# seismo.net
KiCad netlist of a schematic drawn in EAGLE
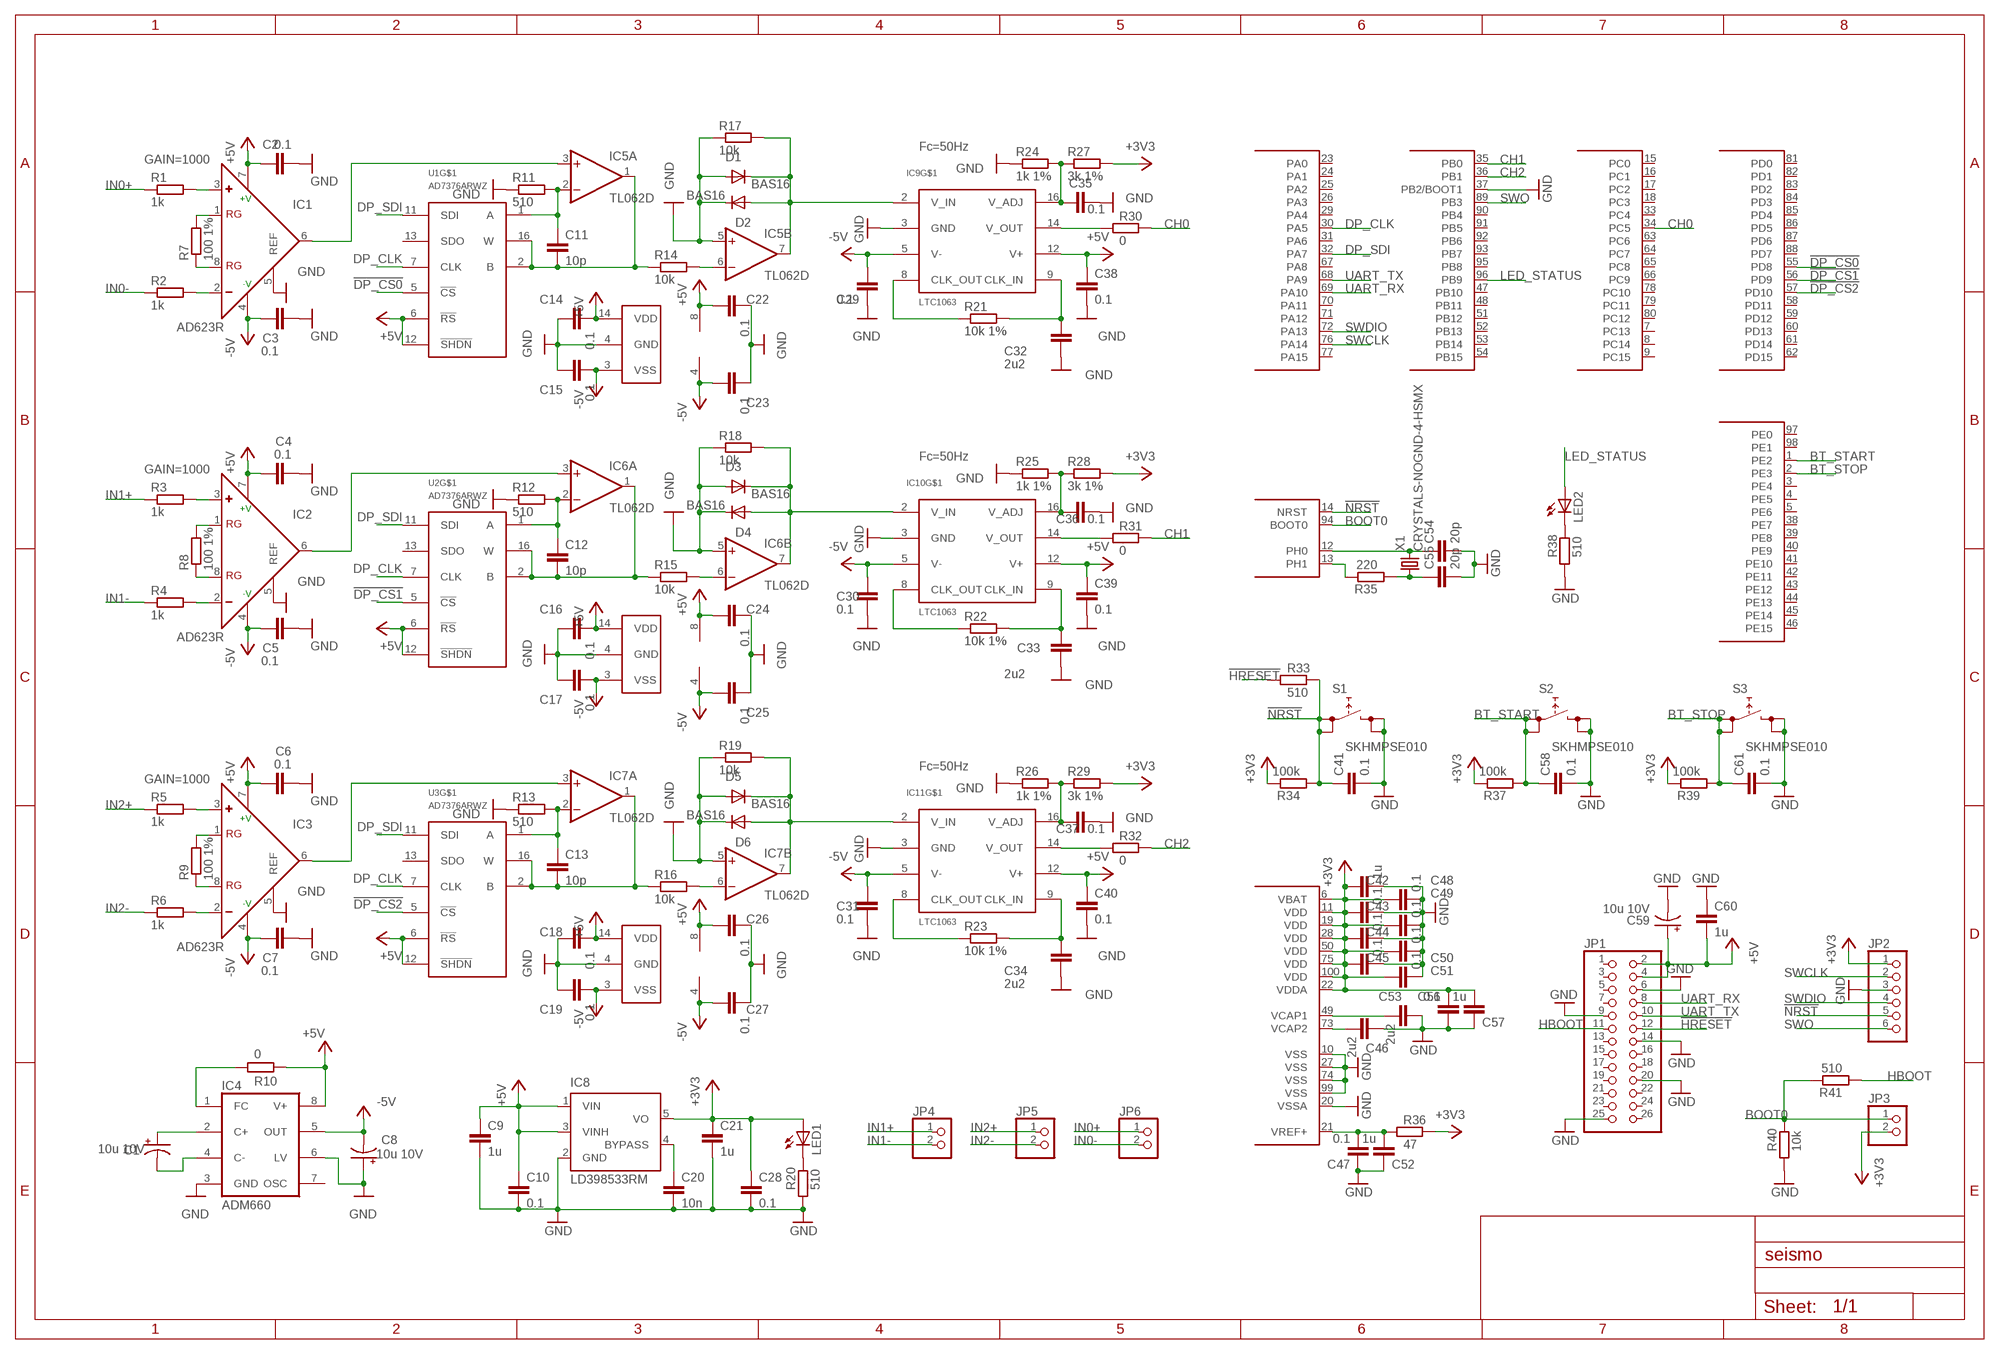
[diagram p0: schematic, sheet 1]

(export (version "E")
  (design (tool "Eeschema 10.0.6"))
  (components
    (comp (ref "C1")
      (value "10u 10V")
      (footprint "eagle-import:SMC_A")
      (libsource (lib "eagle-import") (part "CPOL-USSMCA"))
    )
    (comp (ref "C2")
      (value "0.1")
      (footprint "eagle-import:C0805")
      (libsource (lib "eagle-import") (part "C-EUC0805"))
    )
    (comp (ref "C3")
      (value "0.1")
      (footprint "eagle-import:C0805")
      (libsource (lib "eagle-import") (part "C-EUC0805"))
    )
    (comp (ref "C4")
      (value "0.1")
      (footprint "eagle-import:C0805")
      (libsource (lib "eagle-import") (part "C-EUC0805"))
    )
    (comp (ref "C5")
      (value "0.1")
      (footprint "eagle-import:C0805")
      (libsource (lib "eagle-import") (part "C-EUC0805"))
    )
    (comp (ref "C6")
      (value "0.1")
      (footprint "eagle-import:C0805")
      (libsource (lib "eagle-import") (part "C-EUC0805"))
    )
    (comp (ref "C7")
      (value "0.1")
      (footprint "eagle-import:C0805")
      (libsource (lib "eagle-import") (part "C-EUC0805"))
    )
    (comp (ref "C8")
      (value "10u 10V")
      (footprint "eagle-import:SMC_A")
      (libsource (lib "eagle-import") (part "CPOL-USSMCA"))
    )
    (comp (ref "C9")
      (value "1u")
      (footprint "eagle-import:C0805")
      (libsource (lib "eagle-import") (part "C-EUC0805"))
    )
    (comp (ref "C10")
      (value "0.1")
      (footprint "eagle-import:C0805")
      (libsource (lib "eagle-import") (part "C-EUC0805"))
    )
    (comp (ref "C11")
      (value "10p")
      (footprint "eagle-import:C0805")
      (libsource (lib "eagle-import") (part "C-EUC0805"))
    )
    (comp (ref "C12")
      (value "10p")
      (footprint "eagle-import:C0805")
      (libsource (lib "eagle-import") (part "C-EUC0805"))
    )
    (comp (ref "C13")
      (value "10p")
      (footprint "eagle-import:C0805")
      (libsource (lib "eagle-import") (part "C-EUC0805"))
    )
    (comp (ref "C14")
      (value "0.1")
      (footprint "eagle-import:C0805")
      (libsource (lib "eagle-import") (part "C-EUC0805"))
    )
    (comp (ref "C15")
      (value "0.1")
      (footprint "eagle-import:C0805")
      (libsource (lib "eagle-import") (part "C-EUC0805"))
    )
    (comp (ref "C16")
      (value "0.1")
      (footprint "eagle-import:C0805")
      (libsource (lib "eagle-import") (part "C-EUC0805"))
    )
    (comp (ref "C17")
      (value "0.1")
      (footprint "eagle-import:C0805")
      (libsource (lib "eagle-import") (part "C-EUC0805"))
    )
    (comp (ref "C18")
      (value "0.1")
      (footprint "eagle-import:C0805")
      (libsource (lib "eagle-import") (part "C-EUC0805"))
    )
    (comp (ref "C19")
      (value "0.1")
      (footprint "eagle-import:C0805")
      (libsource (lib "eagle-import") (part "C-EUC0805"))
    )
    (comp (ref "C20")
      (value "10n")
      (footprint "eagle-import:C0805")
      (libsource (lib "eagle-import") (part "C-EUC0805"))
    )
    (comp (ref "C21")
      (value "1u")
      (footprint "eagle-import:C0805")
      (libsource (lib "eagle-import") (part "C-EUC0805"))
    )
    (comp (ref "C22")
      (value "0.1")
      (footprint "eagle-import:C0805")
      (libsource (lib "eagle-import") (part "C-EUC0805"))
    )
    (comp (ref "C23")
      (value "0.1")
      (footprint "eagle-import:C0805")
      (libsource (lib "eagle-import") (part "C-EUC0805"))
    )
    (comp (ref "C24")
      (value "0.1")
      (footprint "eagle-import:C0805")
      (libsource (lib "eagle-import") (part "C-EUC0805"))
    )
    (comp (ref "C25")
      (value "0.1")
      (footprint "eagle-import:C0805")
      (libsource (lib "eagle-import") (part "C-EUC0805"))
    )
    (comp (ref "C26")
      (value "0.1")
      (footprint "eagle-import:C0805")
      (libsource (lib "eagle-import") (part "C-EUC0805"))
    )
    (comp (ref "C27")
      (value "0.1")
      (footprint "eagle-import:C0805")
      (libsource (lib "eagle-import") (part "C-EUC0805"))
    )
    (comp (ref "C28")
      (value "0.1")
      (footprint "eagle-import:C0805")
      (libsource (lib "eagle-import") (part "C-EUC0805"))
    )
    (comp (ref "C29")
      (value "0.1")
      (footprint "eagle-import:C0805")
      (libsource (lib "eagle-import") (part "C-EUC0805"))
    )
    (comp (ref "C30")
      (value "0.1")
      (footprint "eagle-import:C0805")
      (libsource (lib "eagle-import") (part "C-EUC0805"))
    )
    (comp (ref "C31")
      (value "0.1")
      (footprint "eagle-import:C0805")
      (libsource (lib "eagle-import") (part "C-EUC0805"))
    )
    (comp (ref "C32")
      (value "2u2")
      (footprint "eagle-import:C0805")
      (libsource (lib "eagle-import") (part "C-EUC0805"))
    )
    (comp (ref "C33")
      (value "2u2")
      (footprint "eagle-import:C0805")
      (libsource (lib "eagle-import") (part "C-EUC0805"))
    )
    (comp (ref "C34")
      (value "2u2")
      (footprint "eagle-import:C0805")
      (libsource (lib "eagle-import") (part "C-EUC0805"))
    )
    (comp (ref "C35")
      (value "0.1")
      (footprint "eagle-import:C0805")
      (libsource (lib "eagle-import") (part "C-EUC0805"))
    )
    (comp (ref "C36")
      (value "0.1")
      (footprint "eagle-import:C0805")
      (libsource (lib "eagle-import") (part "C-EUC0805"))
    )
    (comp (ref "C37")
      (value "0.1")
      (footprint "eagle-import:C0805")
      (libsource (lib "eagle-import") (part "C-EUC0805"))
    )
    (comp (ref "C38")
      (value "0.1")
      (footprint "eagle-import:C0805")
      (libsource (lib "eagle-import") (part "C-EUC0805"))
    )
    (comp (ref "C39")
      (value "0.1")
      (footprint "eagle-import:C0805")
      (libsource (lib "eagle-import") (part "C-EUC0805"))
    )
    (comp (ref "C40")
      (value "0.1")
      (footprint "eagle-import:C0805")
      (libsource (lib "eagle-import") (part "C-EUC0805"))
    )
    (comp (ref "C41")
      (value "0.1")
      (footprint "eagle-import:C0805")
      (libsource (lib "eagle-import") (part "C-EUC0805"))
    )
    (comp (ref "C42")
      (value "1u")
      (footprint "eagle-import:C0805")
      (libsource (lib "eagle-import") (part "C-EUC0805"))
    )
    (comp (ref "C43")
      (value "0.1")
      (footprint "eagle-import:C0805")
      (libsource (lib "eagle-import") (part "C-EUC0805"))
    )
    (comp (ref "C44")
      (value "0.1")
      (footprint "eagle-import:C0805")
      (libsource (lib "eagle-import") (part "C-EUC0805"))
    )
    (comp (ref "C45")
      (value "0.1")
      (footprint "eagle-import:C0805")
      (libsource (lib "eagle-import") (part "C-EUC0805"))
    )
    (comp (ref "C46")
      (value "2u2")
      (footprint "eagle-import:C0805")
      (libsource (lib "eagle-import") (part "C-EUC0805"))
    )
    (comp (ref "C47")
      (value "0.1")
      (footprint "eagle-import:C0805")
      (libsource (lib "eagle-import") (part "C-EUC0805"))
    )
    (comp (ref "C48")
      (value "0.1")
      (footprint "eagle-import:C0805")
      (libsource (lib "eagle-import") (part "C-EUC0805"))
    )
    (comp (ref "C49")
      (value "0.1")
      (footprint "eagle-import:C0805")
      (libsource (lib "eagle-import") (part "C-EUC0805"))
    )
    (comp (ref "C50")
      (value "0.1")
      (footprint "eagle-import:C0805")
      (libsource (lib "eagle-import") (part "C-EUC0805"))
    )
    (comp (ref "C51")
      (value "0.1")
      (footprint "eagle-import:C0805")
      (libsource (lib "eagle-import") (part "C-EUC0805"))
    )
    (comp (ref "C52")
      (value "1u")
      (footprint "eagle-import:C0805")
      (libsource (lib "eagle-import") (part "C-EUC0805"))
    )
    (comp (ref "C53")
      (value "2u2")
      (footprint "eagle-import:C0805")
      (libsource (lib "eagle-import") (part "C-EUC0805"))
    )
    (comp (ref "C54")
      (value "20p")
      (footprint "eagle-import:C0805")
      (libsource (lib "eagle-import") (part "C-EUC0805"))
    )
    (comp (ref "C55")
      (value "20p")
      (footprint "eagle-import:C0805")
      (libsource (lib "eagle-import") (part "C-EUC0805"))
    )
    (comp (ref "C56")
      (value "0.1")
      (footprint "eagle-import:C0805")
      (libsource (lib "eagle-import") (part "C-EUC0805"))
    )
    (comp (ref "C57")
      (value "1u")
      (footprint "eagle-import:C0805")
      (libsource (lib "eagle-import") (part "C-EUC0805"))
    )
    (comp (ref "C58")
      (value "0.1")
      (footprint "eagle-import:C0805")
      (libsource (lib "eagle-import") (part "C-EUC0805"))
    )
    (comp (ref "C59")
      (value "10u 10V")
      (footprint "eagle-import:SMC_A")
      (libsource (lib "eagle-import") (part "CPOL-USSMCA"))
    )
    (comp (ref "C60")
      (value "1u")
      (footprint "eagle-import:C0805")
      (libsource (lib "eagle-import") (part "C-EUC0805"))
    )
    (comp (ref "C61")
      (value "0.1")
      (footprint "eagle-import:C0805")
      (libsource (lib "eagle-import") (part "C-EUC0805"))
    )
    (comp (ref "D1")
      (value "BAS16")
      (footprint "eagle-import:SOT23")
      (libsource (lib "eagle-import") (part "BAS16"))
    )
    (comp (ref "D2")
      (value "BAS16")
      (footprint "eagle-import:SOT23")
      (libsource (lib "eagle-import") (part "BAS16"))
    )
    (comp (ref "D3")
      (value "BAS16")
      (footprint "eagle-import:SOT23")
      (libsource (lib "eagle-import") (part "BAS16"))
    )
    (comp (ref "D4")
      (value "BAS16")
      (footprint "eagle-import:SOT23")
      (libsource (lib "eagle-import") (part "BAS16"))
    )
    (comp (ref "D5")
      (value "BAS16")
      (footprint "eagle-import:SOT23")
      (libsource (lib "eagle-import") (part "BAS16"))
    )
    (comp (ref "D6")
      (value "BAS16")
      (footprint "eagle-import:SOT23")
      (libsource (lib "eagle-import") (part "BAS16"))
    )
    (comp (ref "IC1")
      (value "AD623R")
      (footprint "eagle-import:SO8")
      (fields (field (name "MPN") "AD623ARZ."))
      (libsource (lib "eagle-import") (part "AD623R"))
    )
    (comp (ref "IC2")
      (value "AD623R")
      (footprint "eagle-import:SO8")
      (fields (field (name "MPN") "AD623ARZ."))
      (libsource (lib "eagle-import") (part "AD623R"))
    )
    (comp (ref "IC3")
      (value "AD623R")
      (footprint "eagle-import:SO8")
      (fields (field (name "MPN") "AD623ARZ."))
      (libsource (lib "eagle-import") (part "AD623R"))
    )
    (comp (ref "IC4")
      (value "ADM660")
      (footprint "eagle-import:SO8")
      (libsource (lib "eagle-import") (part "ADM660"))
    )
    (comp (ref "IC5")
      (value "TL062D")
      (footprint "eagle-import:SO08")
      (libsource (lib "eagle-import") (part "TL062D"))
    )
    (comp (ref "IC6")
      (value "TL062D")
      (footprint "eagle-import:SO08")
      (libsource (lib "eagle-import") (part "TL062D"))
    )
    (comp (ref "IC7")
      (value "TL062D")
      (footprint "eagle-import:SO08")
      (libsource (lib "eagle-import") (part "TL062D"))
    )
    (comp (ref "IC8")
      (value "LD398533RM")
      (footprint "eagle-import:SOT23-5L")
      (libsource (lib "eagle-import") (part "LD3985M33R"))
    )
    (comp (ref "IC9")
      (value "LTC1063")
      (footprint "eagle-import:SOIC127P1032X264-16N")
      (libsource (lib "eagle-import") (part "LTC1063"))
    )
    (comp (ref "IC10")
      (value "LTC1063")
      (footprint "eagle-import:SOIC127P1032X264-16N")
      (libsource (lib "eagle-import") (part "LTC1063"))
    )
    (comp (ref "IC11")
      (value "LTC1063")
      (footprint "eagle-import:SOIC127P1032X264-16N")
      (libsource (lib "eagle-import") (part "LTC1063"))
    )
    (comp (ref "JP1")
      (value "PINHD-2X13")
      (footprint "eagle-import:2X13")
      (libsource (lib "eagle-import") (part "PINHD-2X13"))
    )
    (comp (ref "JP2")
      (value "PINHD-1X6")
      (footprint "eagle-import:1X06")
      (libsource (lib "eagle-import") (part "PINHD-1X6"))
    )
    (comp (ref "JP3")
      (value "PINHD-1X2")
      (footprint "eagle-import:1X02")
      (libsource (lib "eagle-import") (part "PINHD-1X2"))
    )
    (comp (ref "JP4")
      (value "PINHD-1X2")
      (footprint "eagle-import:1X02")
      (libsource (lib "eagle-import") (part "PINHD-1X2"))
    )
    (comp (ref "JP5")
      (value "PINHD-1X2")
      (footprint "eagle-import:1X02")
      (libsource (lib "eagle-import") (part "PINHD-1X2"))
    )
    (comp (ref "JP6")
      (value "PINHD-1X2")
      (footprint "eagle-import:1X02")
      (libsource (lib "eagle-import") (part "PINHD-1X2"))
    )
    (comp (ref "LED1")
      (value "LEDCHIPLED_1206")
      (footprint "eagle-import:CHIPLED_1206")
      (libsource (lib "eagle-import") (part "LEDCHIPLED_1206"))
    )
    (comp (ref "LED2")
      (value "LEDCHIPLED_1206")
      (footprint "eagle-import:CHIPLED_1206")
      (libsource (lib "eagle-import") (part "LEDCHIPLED_1206"))
    )
    (comp (ref "R1")
      (value "1k")
      (footprint "eagle-import:R0805W")
      (libsource (lib "eagle-import") (part "R-EU_R0805W"))
    )
    (comp (ref "R2")
      (value "1k")
      (footprint "eagle-import:R0805W")
      (libsource (lib "eagle-import") (part "R-EU_R0805W"))
    )
    (comp (ref "R3")
      (value "1k")
      (footprint "eagle-import:R0805W")
      (libsource (lib "eagle-import") (part "R-EU_R0805W"))
    )
    (comp (ref "R4")
      (value "1k")
      (footprint "eagle-import:R0805W")
      (libsource (lib "eagle-import") (part "R-EU_R0805W"))
    )
    (comp (ref "R5")
      (value "1k")
      (footprint "eagle-import:R0805W")
      (libsource (lib "eagle-import") (part "R-EU_R0805W"))
    )
    (comp (ref "R6")
      (value "1k")
      (footprint "eagle-import:R0805W")
      (libsource (lib "eagle-import") (part "R-EU_R0805W"))
    )
    (comp (ref "R7")
      (value "100 1%")
      (footprint "eagle-import:R0805W")
      (libsource (lib "eagle-import") (part "R-EU_R0805W"))
    )
    (comp (ref "R8")
      (value "100 1%")
      (footprint "eagle-import:R0805W")
      (libsource (lib "eagle-import") (part "R-EU_R0805W"))
    )
    (comp (ref "R9")
      (value "100 1%")
      (footprint "eagle-import:R0805W")
      (libsource (lib "eagle-import") (part "R-EU_R0805W"))
    )
    (comp (ref "R10")
      (value "0")
      (footprint "eagle-import:R0805W")
      (libsource (lib "eagle-import") (part "R-EU_R0805W"))
    )
    (comp (ref "R11")
      (value "510")
      (footprint "eagle-import:R0805W")
      (libsource (lib "eagle-import") (part "R-EU_R0805W"))
    )
    (comp (ref "R12")
      (value "510")
      (footprint "eagle-import:R0805W")
      (libsource (lib "eagle-import") (part "R-EU_R0805W"))
    )
    (comp (ref "R13")
      (value "510")
      (footprint "eagle-import:R0805W")
      (libsource (lib "eagle-import") (part "R-EU_R0805W"))
    )
    (comp (ref "R14")
      (value "10k")
      (footprint "eagle-import:R0805W")
      (libsource (lib "eagle-import") (part "R-EU_R0805W"))
    )
    (comp (ref "R15")
      (value "10k")
      (footprint "eagle-import:R0805W")
      (libsource (lib "eagle-import") (part "R-EU_R0805W"))
    )
    (comp (ref "R16")
      (value "10k")
      (footprint "eagle-import:R0805W")
      (libsource (lib "eagle-import") (part "R-EU_R0805W"))
    )
    (comp (ref "R17")
      (value "10k")
      (footprint "eagle-import:R0805W")
      (libsource (lib "eagle-import") (part "R-EU_R0805W"))
    )
    (comp (ref "R18")
      (value "10k")
      (footprint "eagle-import:R0805W")
      (libsource (lib "eagle-import") (part "R-EU_R0805W"))
    )
    (comp (ref "R19")
      (value "10k")
      (footprint "eagle-import:R0805W")
      (libsource (lib "eagle-import") (part "R-EU_R0805W"))
    )
    (comp (ref "R20")
      (value "510")
      (footprint "eagle-import:R0805W")
      (libsource (lib "eagle-import") (part "R-EU_R0805W"))
    )
    (comp (ref "R21")
      (value "10k 1%")
      (footprint "eagle-import:R0805W")
      (libsource (lib "eagle-import") (part "R-EU_R0805W"))
    )
    (comp (ref "R22")
      (value "10k 1%")
      (footprint "eagle-import:R0805W")
      (libsource (lib "eagle-import") (part "R-EU_R0805W"))
    )
    (comp (ref "R23")
      (value "10k 1%")
      (footprint "eagle-import:R0805W")
      (libsource (lib "eagle-import") (part "R-EU_R0805W"))
    )
    (comp (ref "R24")
      (value "1k 1%")
      (footprint "eagle-import:R0805W")
      (libsource (lib "eagle-import") (part "R-EU_R0805W"))
    )
    (comp (ref "R25")
      (value "1k 1%")
      (footprint "eagle-import:R0805W")
      (libsource (lib "eagle-import") (part "R-EU_R0805W"))
    )
    (comp (ref "R26")
      (value "1k 1%")
      (footprint "eagle-import:R0805W")
      (libsource (lib "eagle-import") (part "R-EU_R0805W"))
    )
    (comp (ref "R27")
      (value "3k 1%")
      (footprint "eagle-import:R0805W")
      (libsource (lib "eagle-import") (part "R-EU_R0805W"))
    )
    (comp (ref "R28")
      (value "3k 1%")
      (footprint "eagle-import:R0805W")
      (libsource (lib "eagle-import") (part "R-EU_R0805W"))
    )
    (comp (ref "R29")
      (value "3k 1%")
      (footprint "eagle-import:R0805W")
      (libsource (lib "eagle-import") (part "R-EU_R0805W"))
    )
    (comp (ref "R30")
      (value "0")
      (footprint "eagle-import:R0805W")
      (libsource (lib "eagle-import") (part "R-EU_R0805W"))
    )
    (comp (ref "R31")
      (value "0")
      (footprint "eagle-import:R0805W")
      (libsource (lib "eagle-import") (part "R-EU_R0805W"))
    )
    (comp (ref "R32")
      (value "0")
      (footprint "eagle-import:R0805W")
      (libsource (lib "eagle-import") (part "R-EU_R0805W"))
    )
    (comp (ref "R33")
      (value "510")
      (footprint "eagle-import:R0805W")
      (libsource (lib "eagle-import") (part "R-EU_R0805W"))
    )
    (comp (ref "R34")
      (value "100k")
      (footprint "eagle-import:R0805W")
      (libsource (lib "eagle-import") (part "R-EU_R0805W"))
    )
    (comp (ref "R35")
      (value "220")
      (footprint "eagle-import:R0805W")
      (libsource (lib "eagle-import") (part "R-EU_R0805W"))
    )
    (comp (ref "R36")
      (value "47")
      (footprint "eagle-import:R0805W")
      (libsource (lib "eagle-import") (part "R-EU_R0805W"))
    )
    (comp (ref "R37")
      (value "100k")
      (footprint "eagle-import:R0805W")
      (libsource (lib "eagle-import") (part "R-EU_R0805W"))
    )
    (comp (ref "R38")
      (value "510")
      (footprint "eagle-import:R0805W")
      (libsource (lib "eagle-import") (part "R-EU_R0805W"))
    )
    (comp (ref "R39")
      (value "100k")
      (footprint "eagle-import:R0805W")
      (libsource (lib "eagle-import") (part "R-EU_R0805W"))
    )
    (comp (ref "R40")
      (value "10k")
      (footprint "eagle-import:R0805W")
      (libsource (lib "eagle-import") (part "R-EU_R0805W"))
    )
    (comp (ref "R41")
      (value "510")
      (footprint "eagle-import:R0805W")
      (libsource (lib "eagle-import") (part "R-EU_R0805W"))
    )
    (comp (ref "S1")
      (value "SKHMPSE010")
      (footprint "eagle-import:SKHMPXE010")
      (libsource (lib "eagle-import") (part "SKHMPE010S"))
    )
    (comp (ref "S2")
      (value "SKHMPSE010")
      (footprint "eagle-import:SKHMPXE010")
      (libsource (lib "eagle-import") (part "SKHMPE010S"))
    )
    (comp (ref "S3")
      (value "SKHMPSE010")
      (footprint "eagle-import:SKHMPXE010")
      (libsource (lib "eagle-import") (part "SKHMPE010S"))
    )
    (comp (ref "U1")
      (value "AD7376ARWZ")
      (footprint "eagle-import:SO-16W")
      (libsource (lib "eagle-import") (part "AD7376ARWZ"))
    )
    (comp (ref "U2")
      (value "AD7376ARWZ")
      (footprint "eagle-import:SO-16W")
      (libsource (lib "eagle-import") (part "AD7376ARWZ"))
    )
    (comp (ref "U3")
      (value "AD7376ARWZ")
      (footprint "eagle-import:SO-16W")
      (libsource (lib "eagle-import") (part "AD7376ARWZ"))
    )
    (comp (ref "U4")
      (value "STM32F4-100")
      (footprint "eagle-import:SQFP-S-14X14-100")
      (libsource (lib "eagle-import") (part "STM32F4-100"))
    )
    (comp (ref "X1")
      (value "CRYSTALS-NOGND-4-HSMX")
      (footprint "eagle-import:HC49-4-HSMX")
      (libsource (lib "eagle-import") (part "CRYSTALS-NOGND-4-HSMX"))
    )
  )
  (nets
    (net (code "1") (name "+3V3") (class "Default")
      (node (ref "C21") (pin "1") (pinfunction "1_1") (pintype "passive"))
      (node (ref "C28") (pin "1") (pinfunction "1_1") (pintype "passive"))
      (node (ref "C42") (pin "1") (pinfunction "1_1") (pintype "passive"))
      (node (ref "C43") (pin "1") (pinfunction "1_1") (pintype "passive"))
      (node (ref "C44") (pin "1") (pinfunction "1_1") (pintype "passive"))
      (node (ref "C45") (pin "1") (pinfunction "1_1") (pintype "passive"))
      (node (ref "C48") (pin "1") (pinfunction "1_1") (pintype "passive"))
      (node (ref "C49") (pin "1") (pinfunction "1_1") (pintype "passive"))
      (node (ref "C50") (pin "1") (pinfunction "1_1") (pintype "passive"))
      (node (ref "C51") (pin "1") (pinfunction "1_1") (pintype "passive"))
      (node (ref "C56") (pin "2") (pinfunction "2_2") (pintype "passive"))
      (node (ref "C57") (pin "2") (pinfunction "2_2") (pintype "passive"))
      (node (ref "IC8") (pin "5") (pinfunction "VO_5") (pintype "output"))
      (node (ref "JP2") (pin "1") (pinfunction "1_1") (pintype "passive"))
      (node (ref "JP3") (pin "2") (pinfunction "2_2") (pintype "passive"))
      (node (ref "LED1") (pin "A") (pinfunction "A_A") (pintype "passive"))
      (node (ref "R27") (pin "2") (pinfunction "2_2") (pintype "passive"))
      (node (ref "R28") (pin "2") (pinfunction "2_2") (pintype "passive"))
      (node (ref "R29") (pin "2") (pinfunction "2_2") (pintype "passive"))
      (node (ref "R34") (pin "2") (pinfunction "2_2") (pintype "passive"))
      (node (ref "R36") (pin "2") (pinfunction "2_2") (pintype "passive"))
      (node (ref "R37") (pin "2") (pinfunction "2_2") (pintype "passive"))
      (node (ref "R39") (pin "2") (pinfunction "2_2") (pintype "passive"))
      (node (ref "U4") (pin "100") (pinfunction "VDD_100") (pintype "power_in"))
      (node (ref "U4") (pin "11") (pinfunction "VDD_11") (pintype "power_in"))
      (node (ref "U4") (pin "19") (pinfunction "VDD_19") (pintype "power_in"))
      (node (ref "U4") (pin "22") (pinfunction "VDDA_22") (pintype "power_in"))
      (node (ref "U4") (pin "28") (pinfunction "VDD_28") (pintype "power_in"))
      (node (ref "U4") (pin "50") (pinfunction "VDD_50") (pintype "power_in"))
      (node (ref "U4") (pin "6") (pinfunction "VBAT_6") (pintype "power_in"))
      (node (ref "U4") (pin "75") (pinfunction "VDD_75") (pintype "power_in"))
    )
    (net (code "2") (name "+5V") (class "Default")
      (node (ref "C10") (pin "1") (pinfunction "1_1") (pintype "passive"))
      (node (ref "C14") (pin "2") (pinfunction "2_2") (pintype "passive"))
      (node (ref "C16") (pin "2") (pinfunction "2_2") (pintype "passive"))
      (node (ref "C18") (pin "2") (pinfunction "2_2") (pintype "passive"))
      (node (ref "C2") (pin "1") (pinfunction "1_1") (pintype "passive"))
      (node (ref "C22") (pin "1") (pinfunction "1_1") (pintype "passive"))
      (node (ref "C24") (pin "1") (pinfunction "1_1") (pintype "passive"))
      (node (ref "C26") (pin "1") (pinfunction "1_1") (pintype "passive"))
      (node (ref "C38") (pin "1") (pinfunction "1_1") (pintype "passive"))
      (node (ref "C39") (pin "1") (pinfunction "1_1") (pintype "passive"))
      (node (ref "C4") (pin "1") (pinfunction "1_1") (pintype "passive"))
      (node (ref "C40") (pin "1") (pinfunction "1_1") (pintype "passive"))
      (node (ref "C59") (pin "+") (pinfunction "+_+") (pintype "passive"))
      (node (ref "C6") (pin "1") (pinfunction "1_1") (pintype "passive"))
      (node (ref "C60") (pin "2") (pinfunction "2_2") (pintype "passive"))
      (node (ref "C9") (pin "1") (pinfunction "1_1") (pintype "passive"))
      (node (ref "IC1") (pin "7") (pinfunction "+V_7") (pintype "power_in"))
      (node (ref "IC10") (pin "12") (pinfunction "V+_12") (pintype "power_in"))
      (node (ref "IC11") (pin "12") (pinfunction "V+_12") (pintype "power_in"))
      (node (ref "IC2") (pin "7") (pinfunction "+V_7") (pintype "power_in"))
      (node (ref "IC3") (pin "7") (pinfunction "+V_7") (pintype "power_in"))
      (node (ref "IC4") (pin "8") (pinfunction "V+_8") (pintype "power_in"))
      (node (ref "IC5") (pin "8") (pinfunction "V+_8") (pintype "power_in"))
      (node (ref "IC6") (pin "8") (pinfunction "V+_8") (pintype "power_in"))
      (node (ref "IC7") (pin "8") (pinfunction "V+_8") (pintype "power_in"))
      (node (ref "IC8") (pin "1") (pinfunction "VIN_1") (pintype "input"))
      (node (ref "IC8") (pin "3") (pinfunction "VINH_3") (pintype "input"))
      (node (ref "IC9") (pin "12") (pinfunction "V+_12") (pintype "power_in"))
      (node (ref "JP1") (pin "2") (pinfunction "2_2") (pintype "passive"))
      (node (ref "JP1") (pin "4") (pinfunction "4_4") (pintype "passive"))
      (node (ref "R10") (pin "2") (pinfunction "2_2") (pintype "passive"))
      (node (ref "U1") (pin "12") (pinfunction "~{SHDN}_12") (pintype "input"))
      (node (ref "U1") (pin "14") (pinfunction "VDD_14") (pintype "power_in"))
      (node (ref "U1") (pin "6") (pinfunction "~{RS}_6") (pintype "input"))
      (node (ref "U2") (pin "12") (pinfunction "~{SHDN}_12") (pintype "input"))
      (node (ref "U2") (pin "14") (pinfunction "VDD_14") (pintype "power_in"))
      (node (ref "U2") (pin "6") (pinfunction "~{RS}_6") (pintype "input"))
      (node (ref "U3") (pin "12") (pinfunction "~{SHDN}_12") (pintype "input"))
      (node (ref "U3") (pin "14") (pinfunction "VDD_14") (pintype "power_in"))
      (node (ref "U3") (pin "6") (pinfunction "~{RS}_6") (pintype "input"))
    )
    (net (code "3") (name "-5V") (class "Default")
      (node (ref "C15") (pin "2") (pinfunction "2_2") (pintype "passive"))
      (node (ref "C17") (pin "2") (pinfunction "2_2") (pintype "passive"))
      (node (ref "C19") (pin "2") (pinfunction "2_2") (pintype "passive"))
      (node (ref "C23") (pin "1") (pinfunction "1_1") (pintype "passive"))
      (node (ref "C25") (pin "1") (pinfunction "1_1") (pintype "passive"))
      (node (ref "C27") (pin "1") (pinfunction "1_1") (pintype "passive"))
      (node (ref "C29") (pin "1") (pinfunction "1_1") (pintype "passive"))
      (node (ref "C3") (pin "1") (pinfunction "1_1") (pintype "passive"))
      (node (ref "C30") (pin "1") (pinfunction "1_1") (pintype "passive"))
      (node (ref "C31") (pin "1") (pinfunction "1_1") (pintype "passive"))
      (node (ref "C5") (pin "1") (pinfunction "1_1") (pintype "passive"))
      (node (ref "C7") (pin "1") (pinfunction "1_1") (pintype "passive"))
      (node (ref "C8") (pin "-") (pinfunction "-_-") (pintype "passive"))
      (node (ref "IC1") (pin "4") (pinfunction "-V_4") (pintype "power_in"))
      (node (ref "IC10") (pin "5") (pinfunction "V-_5") (pintype "power_in"))
      (node (ref "IC11") (pin "5") (pinfunction "V-_5") (pintype "power_in"))
      (node (ref "IC2") (pin "4") (pinfunction "-V_4") (pintype "power_in"))
      (node (ref "IC3") (pin "4") (pinfunction "-V_4") (pintype "power_in"))
      (node (ref "IC4") (pin "5") (pinfunction "OUT_5") (pintype "power_in"))
      (node (ref "IC5") (pin "4") (pinfunction "V-_4") (pintype "power_in"))
      (node (ref "IC6") (pin "4") (pinfunction "V-_4") (pintype "power_in"))
      (node (ref "IC7") (pin "4") (pinfunction "V-_4") (pintype "power_in"))
      (node (ref "IC9") (pin "5") (pinfunction "V-_5") (pintype "power_in"))
      (node (ref "U1") (pin "3") (pinfunction "VSS_3") (pintype "power_in"))
      (node (ref "U2") (pin "3") (pinfunction "VSS_3") (pintype "power_in"))
      (node (ref "U3") (pin "3") (pinfunction "VSS_3") (pintype "power_in"))
    )
    (net (code "4") (name "/BOOT0") (class "Default")
      (node (ref "JP3") (pin "1") (pinfunction "1_1") (pintype "passive"))
      (node (ref "R40") (pin "2") (pinfunction "2_2") (pintype "passive"))
      (node (ref "R41") (pin "2") (pinfunction "2_2") (pintype "passive"))
      (node (ref "U4") (pin "94") (pinfunction "BOOT0_94") (pintype "bidirectional"))
    )
    (net (code "5") (name "/BT_START") (class "Default")
      (node (ref "C58") (pin "1") (pinfunction "1_1") (pintype "passive"))
      (node (ref "R37") (pin "1") (pinfunction "1_1") (pintype "passive"))
      (node (ref "S2") (pin "1") (pinfunction "1.1_1") (pintype "passive"))
      (node (ref "S2") (pin "2") (pinfunction "1.2_2") (pintype "passive"))
      (node (ref "U4") (pin "1") (pinfunction "PE2_1") (pintype "bidirectional"))
    )
    (net (code "6") (name "/BT_STOP") (class "Default")
      (node (ref "C61") (pin "1") (pinfunction "1_1") (pintype "passive"))
      (node (ref "R39") (pin "1") (pinfunction "1_1") (pintype "passive"))
      (node (ref "S3") (pin "1") (pinfunction "1.1_1") (pintype "passive"))
      (node (ref "S3") (pin "2") (pinfunction "1.2_2") (pintype "passive"))
      (node (ref "U4") (pin "2") (pinfunction "PE3_2") (pintype "bidirectional"))
    )
    (net (code "7") (name "/CH0") (class "Default")
      (node (ref "R30") (pin "2") (pinfunction "2_2") (pintype "passive"))
      (node (ref "U4") (pin "34") (pinfunction "PC5_34") (pintype "bidirectional"))
    )
    (net (code "8") (name "/CH1") (class "Default")
      (node (ref "R31") (pin "2") (pinfunction "2_2") (pintype "passive"))
      (node (ref "U4") (pin "35") (pinfunction "PB0_35") (pintype "bidirectional"))
    )
    (net (code "9") (name "/CH2") (class "Default")
      (node (ref "R32") (pin "2") (pinfunction "2_2") (pintype "passive"))
      (node (ref "U4") (pin "36") (pinfunction "PB1_36") (pintype "bidirectional"))
    )
    (net (code "10") (name "/DP_CLK") (class "Default")
      (node (ref "U1") (pin "7") (pinfunction "CLK_7") (pintype "input"))
      (node (ref "U2") (pin "7") (pinfunction "CLK_7") (pintype "input"))
      (node (ref "U3") (pin "7") (pinfunction "CLK_7") (pintype "input"))
      (node (ref "U4") (pin "30") (pinfunction "PA5_30") (pintype "bidirectional"))
    )
    (net (code "11") (name "/DP_SDI") (class "Default")
      (node (ref "U1") (pin "11") (pinfunction "SDI_11") (pintype "input"))
      (node (ref "U2") (pin "11") (pinfunction "SDI_11") (pintype "input"))
      (node (ref "U3") (pin "11") (pinfunction "SDI_11") (pintype "input"))
      (node (ref "U4") (pin "32") (pinfunction "PA7_32") (pintype "bidirectional"))
    )
    (net (code "12") (name "/HBOOT") (class "Default")
      (node (ref "JP1") (pin "11") (pinfunction "11_11") (pintype "passive"))
      (node (ref "R41") (pin "1") (pinfunction "1_1") (pintype "passive"))
    )
    (net (code "13") (name "/IN0+") (class "Default")
      (node (ref "JP6") (pin "1") (pinfunction "1_1") (pintype "passive"))
      (node (ref "R1") (pin "1") (pinfunction "1_1") (pintype "passive"))
    )
    (net (code "14") (name "/IN0-") (class "Default")
      (node (ref "JP6") (pin "2") (pinfunction "2_2") (pintype "passive"))
      (node (ref "R2") (pin "1") (pinfunction "1_1") (pintype "passive"))
    )
    (net (code "15") (name "/IN1+") (class "Default")
      (node (ref "JP4") (pin "1") (pinfunction "1_1") (pintype "passive"))
      (node (ref "R3") (pin "1") (pinfunction "1_1") (pintype "passive"))
    )
    (net (code "16") (name "/IN1-") (class "Default")
      (node (ref "JP4") (pin "2") (pinfunction "2_2") (pintype "passive"))
      (node (ref "R4") (pin "1") (pinfunction "1_1") (pintype "passive"))
    )
    (net (code "17") (name "/IN2+") (class "Default")
      (node (ref "JP5") (pin "1") (pinfunction "1_1") (pintype "passive"))
      (node (ref "R5") (pin "1") (pinfunction "1_1") (pintype "passive"))
    )
    (net (code "18") (name "/IN2-") (class "Default")
      (node (ref "JP5") (pin "2") (pinfunction "2_2") (pintype "passive"))
      (node (ref "R6") (pin "1") (pinfunction "1_1") (pintype "passive"))
    )
    (net (code "19") (name "/LED_STATUS") (class "Default")
      (node (ref "LED2") (pin "A") (pinfunction "A_A") (pintype "passive"))
      (node (ref "U4") (pin "96") (pinfunction "PB9_96") (pintype "bidirectional"))
    )
    (net (code "20") (name "/SWCLK") (class "Default")
      (node (ref "JP2") (pin "2") (pinfunction "2_2") (pintype "passive"))
      (node (ref "U4") (pin "76") (pinfunction "PA14_76") (pintype "bidirectional"))
    )
    (net (code "21") (name "/SWDIO") (class "Default")
      (node (ref "JP2") (pin "4") (pinfunction "4_4") (pintype "passive"))
      (node (ref "U4") (pin "72") (pinfunction "PA13_72") (pintype "bidirectional"))
    )
    (net (code "22") (name "/SWO") (class "Default")
      (node (ref "JP2") (pin "6") (pinfunction "6_6") (pintype "passive"))
      (node (ref "U4") (pin "89") (pinfunction "PB3_89") (pintype "bidirectional"))
    )
    (net (code "23") (name "/UART_RX") (class "Default")
      (node (ref "JP1") (pin "8") (pinfunction "8_8") (pintype "passive"))
      (node (ref "U4") (pin "69") (pinfunction "PA10_69") (pintype "bidirectional"))
    )
    (net (code "24") (name "/UART_TX") (class "Default")
      (node (ref "JP1") (pin "10") (pinfunction "10_10") (pintype "passive"))
      (node (ref "U4") (pin "68") (pinfunction "PA9_68") (pintype "bidirectional"))
    )
    (net (code "25") (name "/~{DP_CS0}") (class "Default")
      (node (ref "U1") (pin "5") (pinfunction "~{CS}_5") (pintype "input"))
      (node (ref "U4") (pin "55") (pinfunction "PD8_55") (pintype "bidirectional"))
    )
    (net (code "26") (name "/~{DP_CS1}") (class "Default")
      (node (ref "U2") (pin "5") (pinfunction "~{CS}_5") (pintype "input"))
      (node (ref "U4") (pin "56") (pinfunction "PD9_56") (pintype "bidirectional"))
    )
    (net (code "27") (name "/~{DP_CS2}") (class "Default")
      (node (ref "U3") (pin "5") (pinfunction "~{CS}_5") (pintype "input"))
      (node (ref "U4") (pin "57") (pinfunction "PD10_57") (pintype "bidirectional"))
    )
    (net (code "28") (name "/~{HRESET}") (class "Default")
      (node (ref "JP1") (pin "12") (pinfunction "12_12") (pintype "passive"))
      (node (ref "R33") (pin "1") (pinfunction "1_1") (pintype "passive"))
    )
    (net (code "29") (name "/~{NRST}") (class "Default")
      (node (ref "C41") (pin "1") (pinfunction "1_1") (pintype "passive"))
      (node (ref "JP2") (pin "5") (pinfunction "5_5") (pintype "passive"))
      (node (ref "R33") (pin "2") (pinfunction "2_2") (pintype "passive"))
      (node (ref "R34") (pin "1") (pinfunction "1_1") (pintype "passive"))
      (node (ref "S1") (pin "1") (pinfunction "1.1_1") (pintype "passive"))
      (node (ref "S1") (pin "2") (pinfunction "1.2_2") (pintype "passive"))
      (node (ref "U4") (pin "14") (pinfunction "NRST_14") (pintype "bidirectional"))
    )
    (net (code "30") (name "GND") (class "Default")
      (node (ref "C10") (pin "2") (pinfunction "2_2") (pintype "passive"))
      (node (ref "C14") (pin "1") (pinfunction "1_1") (pintype "passive"))
      (node (ref "C15") (pin "1") (pinfunction "1_1") (pintype "passive"))
      (node (ref "C16") (pin "1") (pinfunction "1_1") (pintype "passive"))
      (node (ref "C17") (pin "1") (pinfunction "1_1") (pintype "passive"))
      (node (ref "C18") (pin "1") (pinfunction "1_1") (pintype "passive"))
      (node (ref "C19") (pin "1") (pinfunction "1_1") (pintype "passive"))
      (node (ref "C2") (pin "2") (pinfunction "2_2") (pintype "passive"))
      (node (ref "C20") (pin "2") (pinfunction "2_2") (pintype "passive"))
      (node (ref "C21") (pin "2") (pinfunction "2_2") (pintype "passive"))
      (node (ref "C22") (pin "2") (pinfunction "2_2") (pintype "passive"))
      (node (ref "C23") (pin "2") (pinfunction "2_2") (pintype "passive"))
      (node (ref "C24") (pin "2") (pinfunction "2_2") (pintype "passive"))
      (node (ref "C25") (pin "2") (pinfunction "2_2") (pintype "passive"))
      (node (ref "C26") (pin "2") (pinfunction "2_2") (pintype "passive"))
      (node (ref "C27") (pin "2") (pinfunction "2_2") (pintype "passive"))
      (node (ref "C28") (pin "2") (pinfunction "2_2") (pintype "passive"))
      (node (ref "C29") (pin "2") (pinfunction "2_2") (pintype "passive"))
      (node (ref "C3") (pin "2") (pinfunction "2_2") (pintype "passive"))
      (node (ref "C30") (pin "2") (pinfunction "2_2") (pintype "passive"))
      (node (ref "C31") (pin "2") (pinfunction "2_2") (pintype "passive"))
      (node (ref "C32") (pin "2") (pinfunction "2_2") (pintype "passive"))
      (node (ref "C33") (pin "2") (pinfunction "2_2") (pintype "passive"))
      (node (ref "C34") (pin "2") (pinfunction "2_2") (pintype "passive"))
      (node (ref "C35") (pin "2") (pinfunction "2_2") (pintype "passive"))
      (node (ref "C36") (pin "2") (pinfunction "2_2") (pintype "passive"))
      (node (ref "C37") (pin "2") (pinfunction "2_2") (pintype "passive"))
      (node (ref "C38") (pin "2") (pinfunction "2_2") (pintype "passive"))
      (node (ref "C39") (pin "2") (pinfunction "2_2") (pintype "passive"))
      (node (ref "C4") (pin "2") (pinfunction "2_2") (pintype "passive"))
      (node (ref "C40") (pin "2") (pinfunction "2_2") (pintype "passive"))
      (node (ref "C41") (pin "2") (pinfunction "2_2") (pintype "passive"))
      (node (ref "C42") (pin "2") (pinfunction "2_2") (pintype "passive"))
      (node (ref "C43") (pin "2") (pinfunction "2_2") (pintype "passive"))
      (node (ref "C44") (pin "2") (pinfunction "2_2") (pintype "passive"))
      (node (ref "C45") (pin "2") (pinfunction "2_2") (pintype "passive"))
      (node (ref "C46") (pin "1") (pinfunction "1_1") (pintype "passive"))
      (node (ref "C47") (pin "1") (pinfunction "1_1") (pintype "passive"))
      (node (ref "C48") (pin "2") (pinfunction "2_2") (pintype "passive"))
      (node (ref "C49") (pin "2") (pinfunction "2_2") (pintype "passive"))
      (node (ref "C5") (pin "2") (pinfunction "2_2") (pintype "passive"))
      (node (ref "C50") (pin "2") (pinfunction "2_2") (pintype "passive"))
      (node (ref "C51") (pin "2") (pinfunction "2_2") (pintype "passive"))
      (node (ref "C52") (pin "1") (pinfunction "1_1") (pintype "passive"))
      (node (ref "C53") (pin "1") (pinfunction "1_1") (pintype "passive"))
      (node (ref "C54") (pin "2") (pinfunction "2_2") (pintype "passive"))
      (node (ref "C55") (pin "2") (pinfunction "2_2") (pintype "passive"))
      (node (ref "C56") (pin "1") (pinfunction "1_1") (pintype "passive"))
      (node (ref "C57") (pin "1") (pinfunction "1_1") (pintype "passive"))
      (node (ref "C58") (pin "2") (pinfunction "2_2") (pintype "passive"))
      (node (ref "C59") (pin "-") (pinfunction "-_-") (pintype "passive"))
      (node (ref "C6") (pin "2") (pinfunction "2_2") (pintype "passive"))
      (node (ref "C60") (pin "1") (pinfunction "1_1") (pintype "passive"))
      (node (ref "C61") (pin "2") (pinfunction "2_2") (pintype "passive"))
      (node (ref "C7") (pin "2") (pinfunction "2_2") (pintype "passive"))
      (node (ref "C8") (pin "+") (pinfunction "+_+") (pintype "passive"))
      (node (ref "C9") (pin "2") (pinfunction "2_2") (pintype "passive"))
      (node (ref "D1") (pin "1") (pinfunction "A_1") (pintype "passive"))
      (node (ref "D2") (pin "3") (pinfunction "C_3") (pintype "passive"))
      (node (ref "D3") (pin "1") (pinfunction "A_1") (pintype "passive"))
      (node (ref "D4") (pin "3") (pinfunction "C_3") (pintype "passive"))
      (node (ref "D5") (pin "1") (pinfunction "A_1") (pintype "passive"))
      (node (ref "D6") (pin "3") (pinfunction "C_3") (pintype "passive"))
      (node (ref "IC1") (pin "5") (pinfunction "REF_5") (pintype "passive"))
      (node (ref "IC10") (pin "3") (pinfunction "GND_3") (pintype "power_in"))
      (node (ref "IC11") (pin "3") (pinfunction "GND_3") (pintype "power_in"))
      (node (ref "IC2") (pin "5") (pinfunction "REF_5") (pintype "passive"))
      (node (ref "IC3") (pin "5") (pinfunction "REF_5") (pintype "passive"))
      (node (ref "IC4") (pin "3") (pinfunction "GND_3") (pintype "power_in"))
      (node (ref "IC4") (pin "6") (pinfunction "LV_6") (pintype "passive"))
      (node (ref "IC5") (pin "5") (pinfunction "+IN_5") (pintype "input"))
      (node (ref "IC6") (pin "5") (pinfunction "+IN_5") (pintype "input"))
      (node (ref "IC7") (pin "5") (pinfunction "+IN_5") (pintype "input"))
      (node (ref "IC8") (pin "2") (pinfunction "GND_2") (pintype "power_in"))
      (node (ref "IC9") (pin "3") (pinfunction "GND_3") (pintype "power_in"))
      (node (ref "JP1") (pin "14") (pinfunction "14_14") (pintype "passive"))
      (node (ref "JP1") (pin "20") (pinfunction "20_20") (pintype "passive"))
      (node (ref "JP1") (pin "25") (pinfunction "25_25") (pintype "passive"))
      (node (ref "JP1") (pin "6") (pinfunction "6_6") (pintype "passive"))
      (node (ref "JP1") (pin "9") (pinfunction "9_9") (pintype "passive"))
      (node (ref "JP2") (pin "3") (pinfunction "3_3") (pintype "passive"))
      (node (ref "R11") (pin "1") (pinfunction "1_1") (pintype "passive"))
      (node (ref "R12") (pin "1") (pinfunction "1_1") (pintype "passive"))
      (node (ref "R13") (pin "1") (pinfunction "1_1") (pintype "passive"))
      (node (ref "R17") (pin "1") (pinfunction "1_1") (pintype "passive"))
      (node (ref "R18") (pin "1") (pinfunction "1_1") (pintype "passive"))
      (node (ref "R19") (pin "1") (pinfunction "1_1") (pintype "passive"))
      (node (ref "R20") (pin "1") (pinfunction "1_1") (pintype "passive"))
      (node (ref "R24") (pin "1") (pinfunction "1_1") (pintype "passive"))
      (node (ref "R25") (pin "1") (pinfunction "1_1") (pintype "passive"))
      (node (ref "R26") (pin "1") (pinfunction "1_1") (pintype "passive"))
      (node (ref "R38") (pin "1") (pinfunction "1_1") (pintype "passive"))
      (node (ref "R40") (pin "1") (pinfunction "1_1") (pintype "passive"))
      (node (ref "S1") (pin "3") (pinfunction "2.1_3") (pintype "passive"))
      (node (ref "S1") (pin "4") (pinfunction "2.2_4") (pintype "passive"))
      (node (ref "S2") (pin "3") (pinfunction "2.1_3") (pintype "passive"))
      (node (ref "S2") (pin "4") (pinfunction "2.2_4") (pintype "passive"))
      (node (ref "S3") (pin "3") (pinfunction "2.1_3") (pintype "passive"))
      (node (ref "S3") (pin "4") (pinfunction "2.2_4") (pintype "passive"))
      (node (ref "U1") (pin "4") (pinfunction "GND_4") (pintype "power_in"))
      (node (ref "U2") (pin "4") (pinfunction "GND_4") (pintype "power_in"))
      (node (ref "U3") (pin "4") (pinfunction "GND_4") (pintype "power_in"))
      (node (ref "U4") (pin "10") (pinfunction "VSS_10") (pintype "power_in"))
      (node (ref "U4") (pin "20") (pinfunction "VSSA_20") (pintype "power_in"))
      (node (ref "U4") (pin "27") (pinfunction "VSS_27") (pintype "power_in"))
      (node (ref "U4") (pin "37") (pinfunction "PB2/BOOT1_37") (pintype "bidirectional"))
      (node (ref "U4") (pin "74") (pinfunction "VSS_74") (pintype "power_in"))
      (node (ref "U4") (pin "99") (pinfunction "VSS_99") (pintype "power_in"))
    )
    (net (code "31") (name "Net-(C55-Pad1)") (class "Default")
      (node (ref "C55") (pin "1") (pinfunction "1_1") (pintype "passive"))
      (node (ref "R35") (pin "1") (pinfunction "1_1") (pintype "passive"))
      (node (ref "X1") (pin "1") (pinfunction "1_1") (pintype "passive"))
    )
    (net (code "32") (name "Net-(D1-C)") (class "Default")
      (node (ref "D1") (pin "3") (pinfunction "C_3") (pintype "passive"))
      (node (ref "D2") (pin "1") (pinfunction "A_1") (pintype "passive"))
      (node (ref "IC5") (pin "7") (pinfunction "OUT_7") (pintype "output"))
      (node (ref "IC9") (pin "2") (pinfunction "V_IN_2") (pintype "input"))
      (node (ref "R17") (pin "2") (pinfunction "2_2") (pintype "passive"))
    )
    (net (code "33") (name "Net-(D3-C)") (class "Default")
      (node (ref "D3") (pin "3") (pinfunction "C_3") (pintype "passive"))
      (node (ref "D4") (pin "1") (pinfunction "A_1") (pintype "passive"))
      (node (ref "IC10") (pin "2") (pinfunction "V_IN_2") (pintype "input"))
      (node (ref "IC6") (pin "7") (pinfunction "OUT_7") (pintype "output"))
      (node (ref "R18") (pin "2") (pinfunction "2_2") (pintype "passive"))
    )
    (net (code "34") (name "Net-(D5-C)") (class "Default")
      (node (ref "D5") (pin "3") (pinfunction "C_3") (pintype "passive"))
      (node (ref "D6") (pin "1") (pinfunction "A_1") (pintype "passive"))
      (node (ref "IC11") (pin "2") (pinfunction "V_IN_2") (pintype "input"))
      (node (ref "IC7") (pin "7") (pinfunction "OUT_7") (pintype "output"))
      (node (ref "R19") (pin "2") (pinfunction "2_2") (pintype "passive"))
    )
    (net (code "35") (name "Net-(IC1-+)") (class "Default")
      (node (ref "IC1") (pin "3") (pinfunction "+_3") (pintype "input"))
      (node (ref "R1") (pin "2") (pinfunction "2_2") (pintype "passive"))
    )
    (net (code "36") (name "Net-(IC1--)") (class "Default")
      (node (ref "IC1") (pin "2") (pinfunction "-_2") (pintype "input"))
      (node (ref "R2") (pin "2") (pinfunction "2_2") (pintype "passive"))
    )
    (net (code "37") (name "Net-(IC1-OUT)") (class "Default")
      (node (ref "IC1") (pin "6") (pinfunction "OUT_6") (pintype "output"))
      (node (ref "IC5") (pin "3") (pinfunction "+IN_3") (pintype "input"))
    )
    (net (code "38") (name "Net-(IC1-RG-Pad1)") (class "Default")
      (node (ref "IC1") (pin "1") (pinfunction "RG_1") (pintype "passive"))
      (node (ref "R7") (pin "2") (pinfunction "2_2") (pintype "passive"))
    )
    (net (code "39") (name "Net-(IC1-RG-Pad8)") (class "Default")
      (node (ref "IC1") (pin "8") (pinfunction "RG_8") (pintype "passive"))
      (node (ref "R7") (pin "1") (pinfunction "1_1") (pintype "passive"))
    )
    (net (code "40") (name "Net-(IC2-+)") (class "Default")
      (node (ref "IC2") (pin "3") (pinfunction "+_3") (pintype "input"))
      (node (ref "R3") (pin "2") (pinfunction "2_2") (pintype "passive"))
    )
    (net (code "41") (name "Net-(IC2--)") (class "Default")
      (node (ref "IC2") (pin "2") (pinfunction "-_2") (pintype "input"))
      (node (ref "R4") (pin "2") (pinfunction "2_2") (pintype "passive"))
    )
    (net (code "42") (name "Net-(IC2-OUT)") (class "Default")
      (node (ref "IC2") (pin "6") (pinfunction "OUT_6") (pintype "output"))
      (node (ref "IC6") (pin "3") (pinfunction "+IN_3") (pintype "input"))
    )
    (net (code "43") (name "Net-(IC2-RG-Pad1)") (class "Default")
      (node (ref "IC2") (pin "1") (pinfunction "RG_1") (pintype "passive"))
      (node (ref "R8") (pin "2") (pinfunction "2_2") (pintype "passive"))
    )
    (net (code "44") (name "Net-(IC2-RG-Pad8)") (class "Default")
      (node (ref "IC2") (pin "8") (pinfunction "RG_8") (pintype "passive"))
      (node (ref "R8") (pin "1") (pinfunction "1_1") (pintype "passive"))
    )
    (net (code "45") (name "Net-(IC3-+)") (class "Default")
      (node (ref "IC3") (pin "3") (pinfunction "+_3") (pintype "input"))
      (node (ref "R5") (pin "2") (pinfunction "2_2") (pintype "passive"))
    )
    (net (code "46") (name "Net-(IC3--)") (class "Default")
      (node (ref "IC3") (pin "2") (pinfunction "-_2") (pintype "input"))
      (node (ref "R6") (pin "2") (pinfunction "2_2") (pintype "passive"))
    )
    (net (code "47") (name "Net-(IC3-OUT)") (class "Default")
      (node (ref "IC3") (pin "6") (pinfunction "OUT_6") (pintype "output"))
      (node (ref "IC7") (pin "3") (pinfunction "+IN_3") (pintype "input"))
    )
    (net (code "48") (name "Net-(IC3-RG-Pad1)") (class "Default")
      (node (ref "IC3") (pin "1") (pinfunction "RG_1") (pintype "passive"))
      (node (ref "R9") (pin "2") (pinfunction "2_2") (pintype "passive"))
    )
    (net (code "49") (name "Net-(IC3-RG-Pad8)") (class "Default")
      (node (ref "IC3") (pin "8") (pinfunction "RG_8") (pintype "passive"))
      (node (ref "R9") (pin "1") (pinfunction "1_1") (pintype "passive"))
    )
    (net (code "50") (name "Net-(IC4-C+)") (class "Default")
      (node (ref "C1") (pin "+") (pinfunction "+_+") (pintype "passive"))
      (node (ref "IC4") (pin "2") (pinfunction "C+_2") (pintype "passive"))
    )
    (net (code "51") (name "Net-(IC4-C-)") (class "Default")
      (node (ref "C1") (pin "-") (pinfunction "-_-") (pintype "passive"))
      (node (ref "IC4") (pin "4") (pinfunction "C-_4") (pintype "passive"))
    )
    (net (code "52") (name "Net-(IC4-FC)") (class "Default")
      (node (ref "IC4") (pin "1") (pinfunction "FC_1") (pintype "input"))
      (node (ref "R10") (pin "1") (pinfunction "1_1") (pintype "passive"))
    )
    (net (code "53") (name "Net-(IC5A--IN)") (class "Default")
      (node (ref "C11") (pin "1") (pinfunction "1_1") (pintype "passive"))
      (node (ref "IC5") (pin "2") (pinfunction "-IN_2") (pintype "input"))
      (node (ref "R11") (pin "2") (pinfunction "2_2") (pintype "passive"))
      (node (ref "U1") (pin "1") (pinfunction "A_1") (pintype "bidirectional"))
    )
    (net (code "54") (name "Net-(IC5A-OUT)") (class "Default")
      (node (ref "C11") (pin "2") (pinfunction "2_2") (pintype "passive"))
      (node (ref "IC5") (pin "1") (pinfunction "OUT_1") (pintype "output"))
      (node (ref "R14") (pin "1") (pinfunction "1_1") (pintype "passive"))
      (node (ref "U1") (pin "16") (pinfunction "W_16") (pintype "bidirectional"))
      (node (ref "U1") (pin "2") (pinfunction "B_2") (pintype "bidirectional"))
    )
    (net (code "55") (name "Net-(IC5B--IN)") (class "Default")
      (node (ref "IC5") (pin "6") (pinfunction "-IN_6") (pintype "input"))
      (node (ref "R14") (pin "2") (pinfunction "2_2") (pintype "passive"))
    )
    (net (code "56") (name "Net-(IC6A--IN)") (class "Default")
      (node (ref "C12") (pin "1") (pinfunction "1_1") (pintype "passive"))
      (node (ref "IC6") (pin "2") (pinfunction "-IN_2") (pintype "input"))
      (node (ref "R12") (pin "2") (pinfunction "2_2") (pintype "passive"))
      (node (ref "U2") (pin "1") (pinfunction "A_1") (pintype "bidirectional"))
    )
    (net (code "57") (name "Net-(IC6A-OUT)") (class "Default")
      (node (ref "C12") (pin "2") (pinfunction "2_2") (pintype "passive"))
      (node (ref "IC6") (pin "1") (pinfunction "OUT_1") (pintype "output"))
      (node (ref "R15") (pin "1") (pinfunction "1_1") (pintype "passive"))
      (node (ref "U2") (pin "16") (pinfunction "W_16") (pintype "bidirectional"))
      (node (ref "U2") (pin "2") (pinfunction "B_2") (pintype "bidirectional"))
    )
    (net (code "58") (name "Net-(IC6B--IN)") (class "Default")
      (node (ref "IC6") (pin "6") (pinfunction "-IN_6") (pintype "input"))
      (node (ref "R15") (pin "2") (pinfunction "2_2") (pintype "passive"))
    )
    (net (code "59") (name "Net-(IC7A--IN)") (class "Default")
      (node (ref "C13") (pin "1") (pinfunction "1_1") (pintype "passive"))
      (node (ref "IC7") (pin "2") (pinfunction "-IN_2") (pintype "input"))
      (node (ref "R13") (pin "2") (pinfunction "2_2") (pintype "passive"))
      (node (ref "U3") (pin "1") (pinfunction "A_1") (pintype "bidirectional"))
    )
    (net (code "60") (name "Net-(IC7A-OUT)") (class "Default")
      (node (ref "C13") (pin "2") (pinfunction "2_2") (pintype "passive"))
      (node (ref "IC7") (pin "1") (pinfunction "OUT_1") (pintype "output"))
      (node (ref "R16") (pin "1") (pinfunction "1_1") (pintype "passive"))
      (node (ref "U3") (pin "16") (pinfunction "W_16") (pintype "bidirectional"))
      (node (ref "U3") (pin "2") (pinfunction "B_2") (pintype "bidirectional"))
    )
    (net (code "61") (name "Net-(IC7B--IN)") (class "Default")
      (node (ref "IC7") (pin "6") (pinfunction "-IN_6") (pintype "input"))
      (node (ref "R16") (pin "2") (pinfunction "2_2") (pintype "passive"))
    )
    (net (code "62") (name "Net-(IC8-BYPASS)") (class "Default")
      (node (ref "C20") (pin "1") (pinfunction "1_1") (pintype "passive"))
      (node (ref "IC8") (pin "4") (pinfunction "BYPASS_4") (pintype "passive"))
    )
    (net (code "63") (name "Net-(IC9A-CLK_IN)") (class "Default")
      (node (ref "C32") (pin "1") (pinfunction "1_1") (pintype "passive"))
      (node (ref "IC9") (pin "9") (pinfunction "CLK_IN_9") (pintype "input"))
      (node (ref "R21") (pin "2") (pinfunction "2_2") (pintype "passive"))
    )
    (net (code "64") (name "Net-(IC9A-CLK_OUT)") (class "Default")
      (node (ref "IC9") (pin "8") (pinfunction "CLK_OUT_8") (pintype "output"))
      (node (ref "R21") (pin "1") (pinfunction "1_1") (pintype "passive"))
    )
    (net (code "65") (name "Net-(IC9A-V_ADJ)") (class "Default")
      (node (ref "C35") (pin "1") (pinfunction "1_1") (pintype "passive"))
      (node (ref "IC9") (pin "16") (pinfunction "V_ADJ_16") (pintype "input"))
      (node (ref "R24") (pin "2") (pinfunction "2_2") (pintype "passive"))
      (node (ref "R27") (pin "1") (pinfunction "1_1") (pintype "passive"))
    )
    (net (code "66") (name "Net-(IC9A-V_OUT)") (class "Default")
      (node (ref "IC9") (pin "14") (pinfunction "V_OUT_14") (pintype "output"))
      (node (ref "R30") (pin "1") (pinfunction "1_1") (pintype "passive"))
    )
    (net (code "67") (name "Net-(IC10A-CLK_IN)") (class "Default")
      (node (ref "C33") (pin "1") (pinfunction "1_1") (pintype "passive"))
      (node (ref "IC10") (pin "9") (pinfunction "CLK_IN_9") (pintype "input"))
      (node (ref "R22") (pin "2") (pinfunction "2_2") (pintype "passive"))
    )
    (net (code "68") (name "Net-(IC10A-CLK_OUT)") (class "Default")
      (node (ref "IC10") (pin "8") (pinfunction "CLK_OUT_8") (pintype "output"))
      (node (ref "R22") (pin "1") (pinfunction "1_1") (pintype "passive"))
    )
    (net (code "69") (name "Net-(IC10A-V_ADJ)") (class "Default")
      (node (ref "C36") (pin "1") (pinfunction "1_1") (pintype "passive"))
      (node (ref "IC10") (pin "16") (pinfunction "V_ADJ_16") (pintype "input"))
      (node (ref "R25") (pin "2") (pinfunction "2_2") (pintype "passive"))
      (node (ref "R28") (pin "1") (pinfunction "1_1") (pintype "passive"))
    )
    (net (code "70") (name "Net-(IC10A-V_OUT)") (class "Default")
      (node (ref "IC10") (pin "14") (pinfunction "V_OUT_14") (pintype "output"))
      (node (ref "R31") (pin "1") (pinfunction "1_1") (pintype "passive"))
    )
    (net (code "71") (name "Net-(IC11A-CLK_IN)") (class "Default")
      (node (ref "C34") (pin "1") (pinfunction "1_1") (pintype "passive"))
      (node (ref "IC11") (pin "9") (pinfunction "CLK_IN_9") (pintype "input"))
      (node (ref "R23") (pin "2") (pinfunction "2_2") (pintype "passive"))
    )
    (net (code "72") (name "Net-(IC11A-CLK_OUT)") (class "Default")
      (node (ref "IC11") (pin "8") (pinfunction "CLK_OUT_8") (pintype "output"))
      (node (ref "R23") (pin "1") (pinfunction "1_1") (pintype "passive"))
    )
    (net (code "73") (name "Net-(IC11A-V_ADJ)") (class "Default")
      (node (ref "C37") (pin "1") (pinfunction "1_1") (pintype "passive"))
      (node (ref "IC11") (pin "16") (pinfunction "V_ADJ_16") (pintype "input"))
      (node (ref "R26") (pin "2") (pinfunction "2_2") (pintype "passive"))
      (node (ref "R29") (pin "1") (pinfunction "1_1") (pintype "passive"))
    )
    (net (code "74") (name "Net-(IC11A-V_OUT)") (class "Default")
      (node (ref "IC11") (pin "14") (pinfunction "V_OUT_14") (pintype "output"))
      (node (ref "R32") (pin "1") (pinfunction "1_1") (pintype "passive"))
    )
    (net (code "75") (name "Net-(LED1-PadC)") (class "Default")
      (node (ref "LED1") (pin "C") (pinfunction "C_C") (pintype "passive"))
      (node (ref "R20") (pin "2") (pinfunction "2_2") (pintype "passive"))
    )
    (net (code "76") (name "Net-(LED2-PadC)") (class "Default")
      (node (ref "LED2") (pin "C") (pinfunction "C_C") (pintype "passive"))
      (node (ref "R38") (pin "2") (pinfunction "2_2") (pintype "passive"))
    )
    (net (code "77") (name "Net-(U4A-VCAP1)") (class "Default")
      (node (ref "C53") (pin "2") (pinfunction "2_2") (pintype "passive"))
      (node (ref "U4") (pin "49") (pinfunction "VCAP1_49") (pintype "passive"))
    )
    (net (code "78") (name "Net-(U4A-VCAP2)") (class "Default")
      (node (ref "C46") (pin "2") (pinfunction "2_2") (pintype "passive"))
      (node (ref "U4") (pin "73") (pinfunction "VCAP2_73") (pintype "passive"))
    )
    (net (code "79") (name "Net-(U4A-VREF+)") (class "Default")
      (node (ref "C47") (pin "2") (pinfunction "2_2") (pintype "passive"))
      (node (ref "C52") (pin "2") (pinfunction "2_2") (pintype "passive"))
      (node (ref "R36") (pin "1") (pinfunction "1_1") (pintype "passive"))
      (node (ref "U4") (pin "21") (pinfunction "VREF+_21") (pintype "passive"))
    )
    (net (code "80") (name "Net-(U4G-PH0)") (class "Default")
      (node (ref "C54") (pin "1") (pinfunction "1_1") (pintype "passive"))
      (node (ref "U4") (pin "12") (pinfunction "PH0_12") (pintype "bidirectional"))
      (node (ref "X1") (pin "2") (pinfunction "2_2") (pintype "passive"))
    )
    (net (code "81") (name "Net-(U4G-PH1)") (class "Default")
      (node (ref "R35") (pin "2") (pinfunction "2_2") (pintype "passive"))
      (node (ref "U4") (pin "13") (pinfunction "PH1_13") (pintype "bidirectional"))
    )
    (net (code "82") (name "unconnected-(IC4-OSC-Pad7)") (class "Default")
      (node (ref "IC4") (pin "7") (pinfunction "OSC_7") (pintype "output"))
    )
    (net (code "83") (name "unconnected-(JP1-Pad1)") (class "Default")
      (node (ref "JP1") (pin "1") (pinfunction "1_1") (pintype "passive"))
    )
    (net (code "84") (name "unconnected-(JP1-Pad3)") (class "Default")
      (node (ref "JP1") (pin "3") (pinfunction "3_3") (pintype "passive"))
    )
    (net (code "85") (name "unconnected-(JP1-Pad5)") (class "Default")
      (node (ref "JP1") (pin "5") (pinfunction "5_5") (pintype "passive"))
    )
    (net (code "86") (name "unconnected-(JP1-Pad7)") (class "Default")
      (node (ref "JP1") (pin "7") (pinfunction "7_7") (pintype "passive"))
    )
    (net (code "87") (name "unconnected-(JP1-Pad13)") (class "Default")
      (node (ref "JP1") (pin "13") (pinfunction "13_13") (pintype "passive"))
    )
    (net (code "88") (name "unconnected-(JP1-Pad15)") (class "Default")
      (node (ref "JP1") (pin "15") (pinfunction "15_15") (pintype "passive"))
    )
    (net (code "89") (name "unconnected-(JP1-Pad16)") (class "Default")
      (node (ref "JP1") (pin "16") (pinfunction "16_16") (pintype "passive"))
    )
    (net (code "90") (name "unconnected-(JP1-Pad17)") (class "Default")
      (node (ref "JP1") (pin "17") (pinfunction "17_17") (pintype "passive"))
    )
    (net (code "91") (name "unconnected-(JP1-Pad18)") (class "Default")
      (node (ref "JP1") (pin "18") (pinfunction "18_18") (pintype "passive"))
    )
    (net (code "92") (name "unconnected-(JP1-Pad19)") (class "Default")
      (node (ref "JP1") (pin "19") (pinfunction "19_19") (pintype "passive"))
    )
    (net (code "93") (name "unconnected-(JP1-Pad21)") (class "Default")
      (node (ref "JP1") (pin "21") (pinfunction "21_21") (pintype "passive"))
    )
    (net (code "94") (name "unconnected-(JP1-Pad22)") (class "Default")
      (node (ref "JP1") (pin "22") (pinfunction "22_22") (pintype "passive"))
    )
    (net (code "95") (name "unconnected-(JP1-Pad23)") (class "Default")
      (node (ref "JP1") (pin "23") (pinfunction "23_23") (pintype "passive"))
    )
    (net (code "96") (name "unconnected-(JP1-Pad24)") (class "Default")
      (node (ref "JP1") (pin "24") (pinfunction "24_24") (pintype "passive"))
    )
    (net (code "97") (name "unconnected-(JP1-Pad26)") (class "Default")
      (node (ref "JP1") (pin "26") (pinfunction "26_26") (pintype "passive"))
    )
    (net (code "98") (name "unconnected-(U1A-SDO-Pad13)") (class "Default")
      (node (ref "U1") (pin "13") (pinfunction "SDO_13") (pintype "output"))
    )
    (net (code "99") (name "unconnected-(U2A-SDO-Pad13)") (class "Default")
      (node (ref "U2") (pin "13") (pinfunction "SDO_13") (pintype "output"))
    )
    (net (code "100") (name "unconnected-(U3A-SDO-Pad13)") (class "Default")
      (node (ref "U3") (pin "13") (pinfunction "SDO_13") (pintype "output"))
    )
    (net (code "101") (name "unconnected-(U4B-PA0-Pad23)") (class "Default")
      (node (ref "U4") (pin "23") (pinfunction "PA0_23") (pintype "bidirectional"))
    )
    (net (code "102") (name "unconnected-(U4B-PA1-Pad24)") (class "Default")
      (node (ref "U4") (pin "24") (pinfunction "PA1_24") (pintype "bidirectional"))
    )
    (net (code "103") (name "unconnected-(U4B-PA2-Pad25)") (class "Default")
      (node (ref "U4") (pin "25") (pinfunction "PA2_25") (pintype "bidirectional"))
    )
    (net (code "104") (name "unconnected-(U4B-PA3-Pad26)") (class "Default")
      (node (ref "U4") (pin "26") (pinfunction "PA3_26") (pintype "bidirectional"))
    )
    (net (code "105") (name "unconnected-(U4B-PA4-Pad29)") (class "Default")
      (node (ref "U4") (pin "29") (pinfunction "PA4_29") (pintype "bidirectional"))
    )
    (net (code "106") (name "unconnected-(U4B-PA6-Pad31)") (class "Default")
      (node (ref "U4") (pin "31") (pinfunction "PA6_31") (pintype "bidirectional"))
    )
    (net (code "107") (name "unconnected-(U4B-PA8-Pad67)") (class "Default")
      (node (ref "U4") (pin "67") (pinfunction "PA8_67") (pintype "bidirectional"))
    )
    (net (code "108") (name "unconnected-(U4B-PA11-Pad70)") (class "Default")
      (node (ref "U4") (pin "70") (pinfunction "PA11_70") (pintype "bidirectional"))
    )
    (net (code "109") (name "unconnected-(U4B-PA12-Pad71)") (class "Default")
      (node (ref "U4") (pin "71") (pinfunction "PA12_71") (pintype "bidirectional"))
    )
    (net (code "110") (name "unconnected-(U4B-PA15-Pad77)") (class "Default")
      (node (ref "U4") (pin "77") (pinfunction "PA15_77") (pintype "bidirectional"))
    )
    (net (code "111") (name "unconnected-(U4C-PB4-Pad90)") (class "Default")
      (node (ref "U4") (pin "90") (pinfunction "PB4_90") (pintype "bidirectional"))
    )
    (net (code "112") (name "unconnected-(U4C-PB5-Pad91)") (class "Default")
      (node (ref "U4") (pin "91") (pinfunction "PB5_91") (pintype "bidirectional"))
    )
    (net (code "113") (name "unconnected-(U4C-PB6-Pad92)") (class "Default")
      (node (ref "U4") (pin "92") (pinfunction "PB6_92") (pintype "bidirectional"))
    )
    (net (code "114") (name "unconnected-(U4C-PB7-Pad93)") (class "Default")
      (node (ref "U4") (pin "93") (pinfunction "PB7_93") (pintype "bidirectional"))
    )
    (net (code "115") (name "unconnected-(U4C-PB8-Pad95)") (class "Default")
      (node (ref "U4") (pin "95") (pinfunction "PB8_95") (pintype "bidirectional"))
    )
    (net (code "116") (name "unconnected-(U4C-PB10-Pad47)") (class "Default")
      (node (ref "U4") (pin "47") (pinfunction "PB10_47") (pintype "bidirectional"))
    )
    (net (code "117") (name "unconnected-(U4C-PB11-Pad48)") (class "Default")
      (node (ref "U4") (pin "48") (pinfunction "PB11_48") (pintype "bidirectional"))
    )
    (net (code "118") (name "unconnected-(U4C-PB12-Pad51)") (class "Default")
      (node (ref "U4") (pin "51") (pinfunction "PB12_51") (pintype "bidirectional"))
    )
    (net (code "119") (name "unconnected-(U4C-PB13-Pad52)") (class "Default")
      (node (ref "U4") (pin "52") (pinfunction "PB13_52") (pintype "bidirectional"))
    )
    (net (code "120") (name "unconnected-(U4C-PB14-Pad53)") (class "Default")
      (node (ref "U4") (pin "53") (pinfunction "PB14_53") (pintype "bidirectional"))
    )
    (net (code "121") (name "unconnected-(U4C-PB15-Pad54)") (class "Default")
      (node (ref "U4") (pin "54") (pinfunction "PB15_54") (pintype "bidirectional"))
    )
    (net (code "122") (name "unconnected-(U4D-PC0-Pad15)") (class "Default")
      (node (ref "U4") (pin "15") (pinfunction "PC0_15") (pintype "bidirectional"))
    )
    (net (code "123") (name "unconnected-(U4D-PC1-Pad16)") (class "Default")
      (node (ref "U4") (pin "16") (pinfunction "PC1_16") (pintype "bidirectional"))
    )
    (net (code "124") (name "unconnected-(U4D-PC2-Pad17)") (class "Default")
      (node (ref "U4") (pin "17") (pinfunction "PC2_17") (pintype "bidirectional"))
    )
    (net (code "125") (name "unconnected-(U4D-PC3-Pad18)") (class "Default")
      (node (ref "U4") (pin "18") (pinfunction "PC3_18") (pintype "bidirectional"))
    )
    (net (code "126") (name "unconnected-(U4D-PC4-Pad33)") (class "Default")
      (node (ref "U4") (pin "33") (pinfunction "PC4_33") (pintype "bidirectional"))
    )
    (net (code "127") (name "unconnected-(U4D-PC6-Pad63)") (class "Default")
      (node (ref "U4") (pin "63") (pinfunction "PC6_63") (pintype "bidirectional"))
    )
    (net (code "128") (name "unconnected-(U4D-PC7-Pad64)") (class "Default")
      (node (ref "U4") (pin "64") (pinfunction "PC7_64") (pintype "bidirectional"))
    )
    (net (code "129") (name "unconnected-(U4D-PC8-Pad65)") (class "Default")
      (node (ref "U4") (pin "65") (pinfunction "PC8_65") (pintype "bidirectional"))
    )
    (net (code "130") (name "unconnected-(U4D-PC9-Pad66)") (class "Default")
      (node (ref "U4") (pin "66") (pinfunction "PC9_66") (pintype "bidirectional"))
    )
    (net (code "131") (name "unconnected-(U4D-PC10-Pad78)") (class "Default")
      (node (ref "U4") (pin "78") (pinfunction "PC10_78") (pintype "bidirectional"))
    )
    (net (code "132") (name "unconnected-(U4D-PC11-Pad79)") (class "Default")
      (node (ref "U4") (pin "79") (pinfunction "PC11_79") (pintype "bidirectional"))
    )
    (net (code "133") (name "unconnected-(U4D-PC12-Pad80)") (class "Default")
      (node (ref "U4") (pin "80") (pinfunction "PC12_80") (pintype "bidirectional"))
    )
    (net (code "134") (name "unconnected-(U4D-PC13-Pad7)") (class "Default")
      (node (ref "U4") (pin "7") (pinfunction "PC13_7") (pintype "bidirectional"))
    )
    (net (code "135") (name "unconnected-(U4D-PC14-Pad8)") (class "Default")
      (node (ref "U4") (pin "8") (pinfunction "PC14_8") (pintype "bidirectional"))
    )
    (net (code "136") (name "unconnected-(U4D-PC15-Pad9)") (class "Default")
      (node (ref "U4") (pin "9") (pinfunction "PC15_9") (pintype "bidirectional"))
    )
    (net (code "137") (name "unconnected-(U4E-PD0-Pad81)") (class "Default")
      (node (ref "U4") (pin "81") (pinfunction "PD0_81") (pintype "bidirectional"))
    )
    (net (code "138") (name "unconnected-(U4E-PD1-Pad82)") (class "Default")
      (node (ref "U4") (pin "82") (pinfunction "PD1_82") (pintype "bidirectional"))
    )
    (net (code "139") (name "unconnected-(U4E-PD2-Pad83)") (class "Default")
      (node (ref "U4") (pin "83") (pinfunction "PD2_83") (pintype "bidirectional"))
    )
    (net (code "140") (name "unconnected-(U4E-PD3-Pad84)") (class "Default")
      (node (ref "U4") (pin "84") (pinfunction "PD3_84") (pintype "bidirectional"))
    )
    (net (code "141") (name "unconnected-(U4E-PD4-Pad85)") (class "Default")
      (node (ref "U4") (pin "85") (pinfunction "PD4_85") (pintype "bidirectional"))
    )
    (net (code "142") (name "unconnected-(U4E-PD5-Pad86)") (class "Default")
      (node (ref "U4") (pin "86") (pinfunction "PD5_86") (pintype "bidirectional"))
    )
    (net (code "143") (name "unconnected-(U4E-PD6-Pad87)") (class "Default")
      (node (ref "U4") (pin "87") (pinfunction "PD6_87") (pintype "bidirectional"))
    )
    (net (code "144") (name "unconnected-(U4E-PD7-Pad88)") (class "Default")
      (node (ref "U4") (pin "88") (pinfunction "PD7_88") (pintype "bidirectional"))
    )
    (net (code "145") (name "unconnected-(U4E-PD11-Pad58)") (class "Default")
      (node (ref "U4") (pin "58") (pinfunction "PD11_58") (pintype "bidirectional"))
    )
    (net (code "146") (name "unconnected-(U4E-PD12-Pad59)") (class "Default")
      (node (ref "U4") (pin "59") (pinfunction "PD12_59") (pintype "bidirectional"))
    )
    (net (code "147") (name "unconnected-(U4E-PD13-Pad60)") (class "Default")
      (node (ref "U4") (pin "60") (pinfunction "PD13_60") (pintype "bidirectional"))
    )
    (net (code "148") (name "unconnected-(U4E-PD14-Pad61)") (class "Default")
      (node (ref "U4") (pin "61") (pinfunction "PD14_61") (pintype "bidirectional"))
    )
    (net (code "149") (name "unconnected-(U4E-PD15-Pad62)") (class "Default")
      (node (ref "U4") (pin "62") (pinfunction "PD15_62") (pintype "bidirectional"))
    )
    (net (code "150") (name "unconnected-(U4F-PE0-Pad97)") (class "Default")
      (node (ref "U4") (pin "97") (pinfunction "PE0_97") (pintype "bidirectional"))
    )
    (net (code "151") (name "unconnected-(U4F-PE1-Pad98)") (class "Default")
      (node (ref "U4") (pin "98") (pinfunction "PE1_98") (pintype "bidirectional"))
    )
    (net (code "152") (name "unconnected-(U4F-PE4-Pad3)") (class "Default")
      (node (ref "U4") (pin "3") (pinfunction "PE4_3") (pintype "bidirectional"))
    )
    (net (code "153") (name "unconnected-(U4F-PE5-Pad4)") (class "Default")
      (node (ref "U4") (pin "4") (pinfunction "PE5_4") (pintype "bidirectional"))
    )
    (net (code "154") (name "unconnected-(U4F-PE6-Pad5)") (class "Default")
      (node (ref "U4") (pin "5") (pinfunction "PE6_5") (pintype "bidirectional"))
    )
    (net (code "155") (name "unconnected-(U4F-PE7-Pad38)") (class "Default")
      (node (ref "U4") (pin "38") (pinfunction "PE7_38") (pintype "bidirectional"))
    )
    (net (code "156") (name "unconnected-(U4F-PE8-Pad39)") (class "Default")
      (node (ref "U4") (pin "39") (pinfunction "PE8_39") (pintype "bidirectional"))
    )
    (net (code "157") (name "unconnected-(U4F-PE9-Pad40)") (class "Default")
      (node (ref "U4") (pin "40") (pinfunction "PE9_40") (pintype "bidirectional"))
    )
    (net (code "158") (name "unconnected-(U4F-PE10-Pad41)") (class "Default")
      (node (ref "U4") (pin "41") (pinfunction "PE10_41") (pintype "bidirectional"))
    )
    (net (code "159") (name "unconnected-(U4F-PE11-Pad42)") (class "Default")
      (node (ref "U4") (pin "42") (pinfunction "PE11_42") (pintype "bidirectional"))
    )
    (net (code "160") (name "unconnected-(U4F-PE12-Pad43)") (class "Default")
      (node (ref "U4") (pin "43") (pinfunction "PE12_43") (pintype "bidirectional"))
    )
    (net (code "161") (name "unconnected-(U4F-PE13-Pad44)") (class "Default")
      (node (ref "U4") (pin "44") (pinfunction "PE13_44") (pintype "bidirectional"))
    )
    (net (code "162") (name "unconnected-(U4F-PE14-Pad45)") (class "Default")
      (node (ref "U4") (pin "45") (pinfunction "PE14_45") (pintype "bidirectional"))
    )
    (net (code "163") (name "unconnected-(U4F-PE15-Pad46)") (class "Default")
      (node (ref "U4") (pin "46") (pinfunction "PE15_46") (pintype "bidirectional"))
    )
  )
)
